# kuramoto5.net
KiCad netlist of a schematic drawn in EAGLE
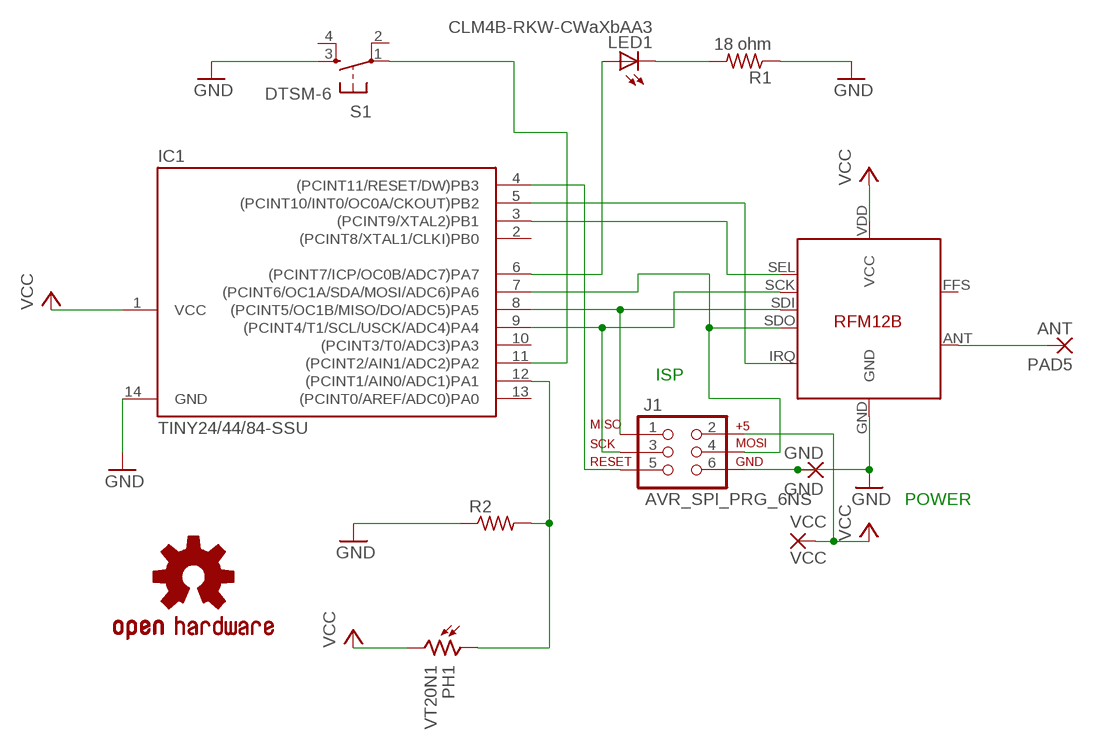
[diagram p0: schematic, sheet 1]

(export (version "E")
  (design (tool "Eeschema 10.0.6"))
  (components
    (comp (ref "GND")
      (value "GND")
      (footprint "eagle-import:2,54_1,0")
      (libsource (lib "eagle-import") (part "WIREPAD2,54/1,0"))
    )
    (comp (ref "IC1")
      (value "TINY24/44/84-SSU")
      (footprint "eagle-import:SOIC14")
      (libsource (lib "eagle-import") (part "TINY24/44/84-SSU"))
    )
    (comp (ref "J1")
      (value "AVR_SPI_PRG_6NS")
      (footprint "eagle-import:2X3-NS")
      (libsource (lib "eagle-import") (part "AVR_SPI_PRG_6NS"))
    )
    (comp (ref "LED1")
      (value "CLM4B-RKW-CWaXbAA3")
      (footprint "eagle-import:P-LCC-4")
      (libsource (lib "eagle-import") (part "LEDP-LCC-4"))
    )
    (comp (ref "PAD5")
      (value "ANT")
      (footprint "eagle-import:2,54_1,0")
      (libsource (lib "eagle-import") (part "WIREPAD2,54/1,0"))
    )
    (comp (ref "PH1")
      (value "VT20N1")
      (footprint "eagle-import:TO46-VT200")
      (libsource (lib "eagle-import") (part "VT20N1"))
    )
    (comp (ref "R1")
      (value "18 ohm")
      (footprint "eagle-import:R0805")
      (libsource (lib "eagle-import") (part "R-US_R0805"))
    )
    (comp (ref "R2")
      (value "R-US_R0805")
      (footprint "eagle-import:R0805")
      (libsource (lib "eagle-import") (part "R-US_R0805"))
    )
    (comp (ref "RFM12B")
      (value "RFM12BN")
      (footprint "eagle-import:RFM12B-NARROW")
      (libsource (lib "eagle-import") (part "RFM12BN"))
    )
    (comp (ref "S1")
      (value "DTSM-6")
      (footprint "eagle-import:DTSM-6")
      (libsource (lib "eagle-import") (part "DTSM-6"))
    )
    (comp (ref "U$1")
      (value "OSHW-LOGOS")
      (footprint "eagle-import:OSHW-LOGO-S")
      (libsource (lib "eagle-import") (part "OSHW-LOGOS"))
    )
    (comp (ref "VCC")
      (value "VCC")
      (footprint "eagle-import:2,54_1,0")
      (libsource (lib "eagle-import") (part "WIREPAD2,54/1,0"))
    )
  )
  (nets
    (net (code "1") (name "GND") (class "Default")
      (node (ref "GND") (pin "1") (pinfunction "P_1") (pintype "passive"))
      (node (ref "IC1") (pin "14") (pinfunction "GND_14") (pintype "power_in"))
      (node (ref "J1") (pin "6") (pinfunction "6_6") (pintype "passive"))
      (node (ref "R1") (pin "1") (pinfunction "1_1") (pintype "passive"))
      (node (ref "R2") (pin "1") (pinfunction "1_1") (pintype "passive"))
      (node (ref "RFM12B") (pin "GND") (pinfunction "GND_GND") (pintype "power_in"))
      (node (ref "S1") (pin "3") (pinfunction "3_3") (pintype "passive"))
    )
    (net (code "2") (name "Net-(IC1-(PCINT1{slash}AIN0{slash}ADC1)PA1)") (class "Default")
      (node (ref "IC1") (pin "12") (pinfunction "(PCINT1/AIN0/ADC1)PA1_12") (pintype "bidirectional"))
      (node (ref "PH1") (pin "1") (pinfunction "1_1") (pintype "passive"))
      (node (ref "R2") (pin "2") (pinfunction "2_2") (pintype "passive"))
    )
    (net (code "3") (name "Net-(IC1-(PCINT2{slash}AIN1{slash}ADC2)PA2)") (class "Default")
      (node (ref "IC1") (pin "11") (pinfunction "(PCINT2/AIN1/ADC2)PA2_11") (pintype "bidirectional"))
      (node (ref "S1") (pin "1") (pinfunction "1_1") (pintype "passive"))
    )
    (net (code "4") (name "Net-(IC1-(PCINT4{slash}T1{slash}SCL{slash}USCK{slash}ADC4)PA4)") (class "Default")
      (node (ref "IC1") (pin "9") (pinfunction "(PCINT4/T1/SCL/USCK/ADC4)PA4_9") (pintype "bidirectional"))
      (node (ref "J1") (pin "3") (pinfunction "3_3") (pintype "passive"))
      (node (ref "RFM12B") (pin "SCK") (pinfunction "SCK_SCK") (pintype "input"))
    )
    (net (code "5") (name "Net-(IC1-(PCINT5{slash}OC1B{slash}MISO{slash}DO{slash}ADC5)PA5)") (class "Default")
      (node (ref "IC1") (pin "8") (pinfunction "(PCINT5/OC1B/MISO/DO/ADC5)PA5_8") (pintype "bidirectional"))
      (node (ref "J1") (pin "1") (pinfunction "1_1") (pintype "passive"))
      (node (ref "RFM12B") (pin "SDI") (pinfunction "SDI_SDI") (pintype "input"))
    )
    (net (code "6") (name "Net-(IC1-(PCINT6{slash}OC1A{slash}SDA{slash}MOSI{slash}ADC6)PA6)") (class "Default")
      (node (ref "IC1") (pin "7") (pinfunction "(PCINT6/OC1A/SDA/MOSI/ADC6)PA6_7") (pintype "bidirectional"))
      (node (ref "J1") (pin "4") (pinfunction "4_4") (pintype "passive"))
      (node (ref "RFM12B") (pin "SDO") (pinfunction "SDO_SDO") (pintype "output"))
    )
    (net (code "7") (name "Net-(IC1-(PCINT7{slash}ICP{slash}OC0B{slash}ADC7)PA7)") (class "Default")
      (node (ref "IC1") (pin "6") (pinfunction "(PCINT7/ICP/OC0B/ADC7)PA7_6") (pintype "bidirectional"))
      (node (ref "LED1") (pin "A") (pinfunction "A_A") (pintype "passive"))
    )
    (net (code "8") (name "Net-(IC1-(PCINT9{slash}XTAL2)PB1)") (class "Default")
      (node (ref "IC1") (pin "3") (pinfunction "(PCINT9/XTAL2)PB1_3") (pintype "bidirectional"))
      (node (ref "RFM12B") (pin "SEL") (pinfunction "SEL_SEL") (pintype "input"))
    )
    (net (code "9") (name "Net-(IC1-(PCINT10{slash}INT0{slash}OC0A{slash}CKOUT)PB2)") (class "Default")
      (node (ref "IC1") (pin "5") (pinfunction "(PCINT10/INT0/OC0A/CKOUT)PB2_5") (pintype "bidirectional"))
      (node (ref "RFM12B") (pin "IRQ") (pinfunction "IRQ_IRQ") (pintype "open_collector"))
    )
    (net (code "10") (name "Net-(IC1-(PCINT11{slash}RESET{slash}DW)PB3)") (class "Default")
      (node (ref "IC1") (pin "4") (pinfunction "(PCINT11/RESET/DW)PB3_4") (pintype "bidirectional"))
      (node (ref "J1") (pin "5") (pinfunction "5_5") (pintype "passive"))
    )
    (net (code "11") (name "Net-(LED1-C)") (class "Default")
      (node (ref "LED1") (pin "C@4") (pinfunction "C_C@4") (pintype "passive"))
      (node (ref "R1") (pin "2") (pinfunction "2_2") (pintype "passive"))
    )
    (net (code "12") (name "Net-(PAD5-P)") (class "Default")
      (node (ref "PAD5") (pin "1") (pinfunction "P_1") (pintype "passive"))
      (node (ref "RFM12B") (pin "ANT") (pinfunction "ANT_ANT") (pintype "passive"))
    )
    (net (code "13") (name "VCC") (class "Default")
      (node (ref "IC1") (pin "1") (pinfunction "VCC_1") (pintype "power_in"))
      (node (ref "J1") (pin "2") (pinfunction "2_2") (pintype "passive"))
      (node (ref "PH1") (pin "2") (pinfunction "2_2") (pintype "passive"))
      (node (ref "RFM12B") (pin "VDD") (pinfunction "VCC_VDD") (pintype "power_in"))
      (node (ref "VCC") (pin "1") (pinfunction "P_1") (pintype "passive"))
    )
    (net (code "14") (name "unconnected-(IC1-(PCINT0{slash}AREF{slash}ADC0)PA0-Pad13)") (class "Default")
      (node (ref "IC1") (pin "13") (pinfunction "(PCINT0/AREF/ADC0)PA0_13") (pintype "bidirectional"))
    )
    (net (code "15") (name "unconnected-(IC1-(PCINT3{slash}T0{slash}ADC3)PA3-Pad10)") (class "Default")
      (node (ref "IC1") (pin "10") (pinfunction "(PCINT3/T0/ADC3)PA3_10") (pintype "bidirectional"))
    )
    (net (code "16") (name "unconnected-(IC1-(PCINT8{slash}XTAL1{slash}CLKI)PB0-Pad2)") (class "Default")
      (node (ref "IC1") (pin "2") (pinfunction "(PCINT8/XTAL1/CLKI)PB0_2") (pintype "bidirectional"))
    )
    (net (code "17") (name "unconnected-(RFM12B-PadFFS)") (class "Default")
      (node (ref "RFM12B") (pin "FFS") (pinfunction "FFS_FFS") (pintype "bidirectional"))
    )
    (net (code "18") (name "unconnected-(S1-Pad2)") (class "Default")
      (node (ref "S1") (pin "2") (pinfunction "2_2") (pintype "passive"))
    )
    (net (code "19") (name "unconnected-(S1-Pad4)") (class "Default")
      (node (ref "S1") (pin "4") (pinfunction "4_4") (pintype "passive"))
    )
  )
)
